# xuefei_zhiye-lab7.net
KiCad netlist of a schematic drawn in EAGLE
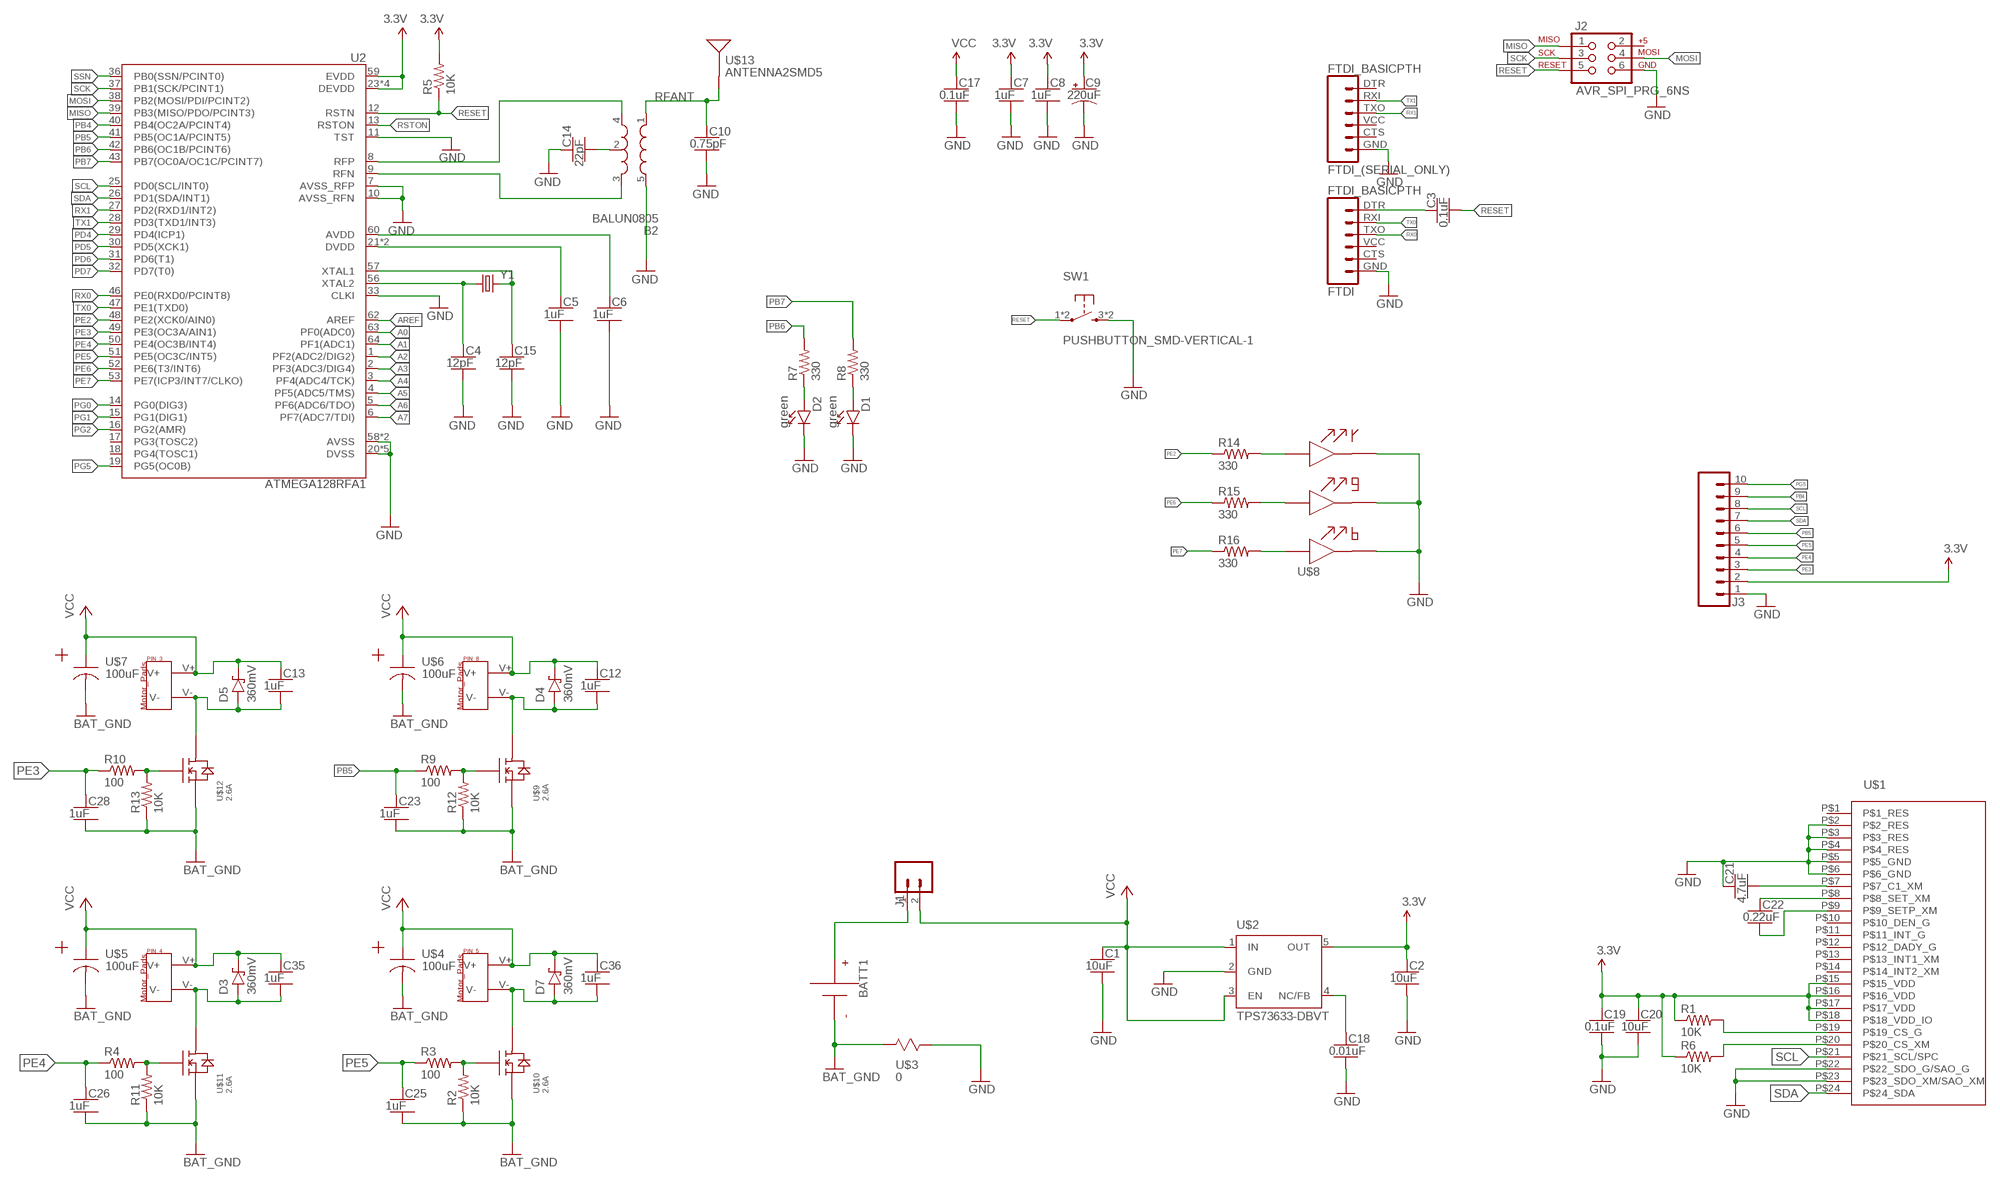
[diagram p0: schematic, sheet 1]

(export (version "E")
  (design (tool "Eeschema 10.0.6"))
  (components
    (comp (ref "B2")
      (value "BALUN0805")
      (footprint "eagle-import:BALUN")
      (fields (field (name "MFR") "Wurth Electronics Inc") (field (name "MPN") "748421245"))
      (libsource (lib "eagle-import") (part "BALUN0805"))
    )
    (comp (ref "BATT1")
      (value "BATTERY-HUBSAN-W/HOLDER")
      (footprint "eagle-import:BATTERY-W_HOLDER-380MAH-HUBSAN")
      (fields
        (field (name "MFR") "HUBSAN")
        (field (name "MPN") "X4-H107C-8-in-1")
        (field (name "CREATOR") "Swanson")
      )
      (libsource (lib "eagle-import") (part "BATTERY-HUBSAN-W/HOLDER"))
    )
    (comp (ref "C1")
      (value "10uF")
      (footprint "eagle-import:CAPC2012X140_HS")
      (fields
        (field (name "MFR") "Murata Electronics North America")
        (field (name "MPN") "GRM21BR61E106KA73L")
      )
      (libsource (lib "eagle-import") (part "CAPACITOR-NP_SMD-2012-0805_CERAMIC-10UF"))
    )
    (comp (ref "C2")
      (value "10uF")
      (footprint "eagle-import:CAPC2012X140_HS")
      (fields
        (field (name "MFR") "Murata Electronics North America")
        (field (name "MPN") "GRM21BR61E106KA73L")
      )
      (libsource (lib "eagle-import") (part "CAPACITOR-NP_SMD-2012-0805_CERAMIC-10UF"))
    )
    (comp (ref "C3")
      (value "0.1uF")
      (footprint "eagle-import:CAPC2012X140_HS")
      (fields
        (field (name "MFR") "Murata Electronics North America")
        (field (name "MPN") "GRM21BR71H104KA01L")
      )
      (libsource (lib "eagle-import") (part "CAPACITOR-NP_SMD-2012-0805_CERAMIC-0.1UF"))
    )
    (comp (ref "C4")
      (value "12pF")
      (footprint "eagle-import:CAPC2012X140_HS")
      (fields
        (field (name "MFR") "Murata Electronics North America")
        (field (name "MPN") "GRM21A5C2E120JW01D")
      )
      (libsource (lib "eagle-import") (part "CAPACITOR-NP_SMD-2012-0805_CERAMIC-12PF"))
    )
    (comp (ref "C5")
      (value "1uF")
      (footprint "eagle-import:CAPC2012X140_HS")
      (fields
        (field (name "MFR") "Murata Electronics North America")
        (field (name "MPN") "GRM21BR71H105KA12L")
      )
      (libsource (lib "eagle-import") (part "CAPACITOR-NP_SMD-2012-0805_CERAMIC-1UF"))
    )
    (comp (ref "C6")
      (value "1uF")
      (footprint "eagle-import:CAPC2012X140_HS")
      (fields
        (field (name "MFR") "Murata Electronics North America")
        (field (name "MPN") "GRM21BR71H105KA12L")
      )
      (libsource (lib "eagle-import") (part "CAPACITOR-NP_SMD-2012-0805_CERAMIC-1UF"))
    )
    (comp (ref "C7")
      (value "1uF")
      (footprint "eagle-import:CAPC2012X140_HS")
      (fields
        (field (name "MFR") "Murata Electronics North America")
        (field (name "MPN") "GRM21BR71H105KA12L")
      )
      (libsource (lib "eagle-import") (part "CAPACITOR-NP_SMD-2012-0805_CERAMIC-1UF"))
    )
    (comp (ref "C8")
      (value "1uF")
      (footprint "eagle-import:CAPC2012X140_HS")
      (fields
        (field (name "MFR") "Murata Electronics North America")
        (field (name "MPN") "GRM21BR71H105KA12L")
      )
      (libsource (lib "eagle-import") (part "CAPACITOR-NP_SMD-2012-0805_CERAMIC-1UF"))
    )
    (comp (ref "C9")
      (value "220uF")
      (footprint "eagle-import:CAPMP7343X310_HS")
      (fields (field (name "MFR") "AVX Corporation") (field (name "MPN") "TAJD227K006RNJ"))
      (libsource (lib "eagle-import") (part "CAPACITOR-POL_SMD-7043-D_TANTALUM-220UF"))
    )
    (comp (ref "C10")
      (value "0.75pF")
      (footprint "eagle-import:CAPC2012X140_HS")
      (fields
        (field (name "MFR") "Murata Electronics North America")
        (field (name "MPN") "GQM2195C2AR75CB01D")
      )
      (libsource (lib "eagle-import") (part "CAPACITOR-NP_SMD-2012-0805_CERAMIC-0.75PF"))
    )
    (comp (ref "C12")
      (value "1uF")
      (footprint "eagle-import:CAPC2012X140_HS")
      (fields
        (field (name "MFR") "Murata Electronics North America")
        (field (name "MPN") "GRM21BR71H105KA12L")
      )
      (libsource (lib "eagle-import") (part "CAPACITOR-NP_SMD-2012-0805_CERAMIC-1UF"))
    )
    (comp (ref "C13")
      (value "1uF")
      (footprint "eagle-import:CAPC2012X140_HS")
      (fields
        (field (name "MFR") "Murata Electronics North America")
        (field (name "MPN") "GRM21BR71H105KA12L")
      )
      (libsource (lib "eagle-import") (part "CAPACITOR-NP_SMD-2012-0805_CERAMIC-1UF"))
    )
    (comp (ref "C14")
      (value "22pF")
      (footprint "eagle-import:CAPC2012X140_HS")
      (fields
        (field (name "MFR") "Murata Electronics North America")
        (field (name "MPN") "GRM21A5C2E220JW01D")
      )
      (libsource (lib "eagle-import") (part "CAPACITOR-NP_SMD-2012-0805_CERAMIC-22PF"))
    )
    (comp (ref "C15")
      (value "12pF")
      (footprint "eagle-import:CAPC2012X140_HS")
      (fields
        (field (name "MFR") "Murata Electronics North America")
        (field (name "MPN") "GRM21A5C2E120JW01D")
      )
      (libsource (lib "eagle-import") (part "CAPACITOR-NP_SMD-2012-0805_CERAMIC-12PF"))
    )
    (comp (ref "C17")
      (value "0.1uF")
      (footprint "eagle-import:CAPC2012X140_HS")
      (fields
        (field (name "MFR") "Murata Electronics North America")
        (field (name "MPN") "GRM21BR71H104KA01L")
      )
      (libsource (lib "eagle-import") (part "CAPACITOR-NP_SMD-2012-0805_CERAMIC-0.1UF"))
    )
    (comp (ref "C18")
      (value "0.01uF")
      (footprint "eagle-import:CAPC2012X140_HS")
      (fields
        (field (name "MFR") "Murata Electronics North America")
        (field (name "MPN") "GRM2195C1H103FA01D")
      )
      (libsource (lib "eagle-import") (part "CAPACITOR-NP_SMD-2012-0805_CERAMIC-0.01UF"))
    )
    (comp (ref "C19")
      (value "0.1uF")
      (footprint "eagle-import:CAPC2012X140_HS")
      (fields
        (field (name "MFR") "Murata Electronics North America")
        (field (name "MPN") "GRM21BR71H104KA01L")
      )
      (libsource (lib "eagle-import") (part "CAPACITOR-NP_SMD-2012-0805_CERAMIC-0.1UF"))
    )
    (comp (ref "C20")
      (value "10uF")
      (footprint "eagle-import:CAPC2012X140_HS")
      (fields
        (field (name "MFR") "Murata Electronics North America")
        (field (name "MPN") "GRM21BR61E106KA73L")
      )
      (libsource (lib "eagle-import") (part "CAPACITOR-NP_SMD-2012-0805_CERAMIC-10UF"))
    )
    (comp (ref "C21")
      (value "4.7uF")
      (footprint "eagle-import:CAPC2012X140_HS")
      (fields
        (field (name "MFR") "Murata Electronics North America")
        (field (name "MPN") "GRM21BR61E475KA12L")
      )
      (libsource (lib "eagle-import") (part "CAPACITOR-NP_SMD-2012-0805_CERAMIC-4.7UF"))
    )
    (comp (ref "C22")
      (value "0.22uF")
      (footprint "eagle-import:CAPC2012X140_HS")
      (fields
        (field (name "MFR") "Murata Electronics North America")
        (field (name "MPN") "GRM21BR71H224KA01L")
      )
      (libsource (lib "eagle-import") (part "CAPACITOR-NP_SMD-2012-0805_CERAMIC-0.22UF"))
    )
    (comp (ref "C23")
      (value "1uF")
      (footprint "eagle-import:CAPC2012X140_HS")
      (fields
        (field (name "MFR") "Murata Electronics North America")
        (field (name "MPN") "GRM21BR71H105KA12L")
      )
      (libsource (lib "eagle-import") (part "CAPACITOR-NP_SMD-2012-0805_CERAMIC-1UF"))
    )
    (comp (ref "C25")
      (value "1uF")
      (footprint "eagle-import:CAPC2012X140_HS")
      (fields
        (field (name "MFR") "Murata Electronics North America")
        (field (name "MPN") "GRM21BR71H105KA12L")
      )
      (libsource (lib "eagle-import") (part "CAPACITOR-NP_SMD-2012-0805_CERAMIC-1UF"))
    )
    (comp (ref "C26")
      (value "1uF")
      (footprint "eagle-import:CAPC2012X140_HS")
      (fields
        (field (name "MFR") "Murata Electronics North America")
        (field (name "MPN") "GRM21BR71H105KA12L")
      )
      (libsource (lib "eagle-import") (part "CAPACITOR-NP_SMD-2012-0805_CERAMIC-1UF"))
    )
    (comp (ref "C28")
      (value "1uF")
      (footprint "eagle-import:CAPC2012X140_HS")
      (fields
        (field (name "MFR") "Murata Electronics North America")
        (field (name "MPN") "GRM21BR71H105KA12L")
      )
      (libsource (lib "eagle-import") (part "CAPACITOR-NP_SMD-2012-0805_CERAMIC-1UF"))
    )
    (comp (ref "C35")
      (value "1uF")
      (footprint "eagle-import:CAPC2012X140_HS")
      (fields
        (field (name "MFR") "Murata Electronics North America")
        (field (name "MPN") "GRM21BR71H105KA12L")
      )
      (libsource (lib "eagle-import") (part "CAPACITOR-NP_SMD-2012-0805_CERAMIC-1UF"))
    )
    (comp (ref "C36")
      (value "1uF")
      (footprint "eagle-import:CAPC2012X140_HS")
      (fields
        (field (name "MFR") "Murata Electronics North America")
        (field (name "MPN") "GRM21BR71H105KA12L")
      )
      (libsource (lib "eagle-import") (part "CAPACITOR-NP_SMD-2012-0805_CERAMIC-1UF"))
    )
    (comp (ref "D1")
      (value "green")
      (footprint "eagle-import:LEDSC125X200X120-2_HS")
      (fields (field (name "MFR") "Lite-On Inc") (field (name "MPN") "LTST-C170GKT"))
      (libsource (lib "eagle-import") (part "DIODE-LED_SMD-2012-0805-GREEN"))
    )
    (comp (ref "D2")
      (value "green")
      (footprint "eagle-import:LEDSC125X200X120-2_HS")
      (fields (field (name "MFR") "Lite-On Inc") (field (name "MPN") "LTST-C170GKT"))
      (libsource (lib "eagle-import") (part "DIODE-LED_SMD-2012-0805-GREEN"))
    )
    (comp (ref "D3")
      (value "360mV")
      (footprint "eagle-import:SOD3716X135_HS")
      (fields
        (field (name "MFR") "Toshiba Semiconductor and Storage")
        (field (name "MPN") "CRS08(TE85L,Q,M)")
      )
      (libsource (lib "eagle-import") (part "DIODE-SCHOTTKY_SMD-SOD123-360MV"))
    )
    (comp (ref "D4")
      (value "360mV")
      (footprint "eagle-import:SOD3716X135_HS")
      (fields
        (field (name "MFR") "Toshiba Semiconductor and Storage")
        (field (name "MPN") "CRS08(TE85L,Q,M)")
      )
      (libsource (lib "eagle-import") (part "DIODE-SCHOTTKY_SMD-SOD123-360MV"))
    )
    (comp (ref "D5")
      (value "360mV")
      (footprint "eagle-import:SOD3716X135_HS")
      (fields
        (field (name "MFR") "Toshiba Semiconductor and Storage")
        (field (name "MPN") "CRS08(TE85L,Q,M)")
      )
      (libsource (lib "eagle-import") (part "DIODE-SCHOTTKY_SMD-SOD123-360MV"))
    )
    (comp (ref "D7")
      (value "360mV")
      (footprint "eagle-import:SOD3716X135_HS")
      (fields
        (field (name "MFR") "Toshiba Semiconductor and Storage")
        (field (name "MPN") "CRS08(TE85L,Q,M)")
      )
      (libsource (lib "eagle-import") (part "DIODE-SCHOTTKY_SMD-SOD123-360MV"))
    )
    (comp (ref "FTDI")
      (value "FTDI_BASICPTH")
      (footprint "eagle-import:FTDI_BASIC")
      (fields (field (name "MFR") "Amphenol FCI") (field (name "MPN") "68016-406HLF"))
      (libsource (lib "eagle-import") (part "FTDI_BASICPTH"))
    )
    (comp (ref "FTDI_(SERIAL_ONLY)")
      (value "FTDI_BASICPTH")
      (footprint "eagle-import:FTDI_BASIC")
      (fields (field (name "MFR") "Amphenol FCI") (field (name "MPN") "68016-406HLF"))
      (libsource (lib "eagle-import") (part "FTDI_BASICPTH"))
    )
    (comp (ref "J1")
      (value "MALE_HEADER_2POS-2X1-0.1IN")
      (footprint "eagle-import:MALE_HEADER_2X1_0.1IN")
      (fields
        (field (name "MFR") "3M")
        (field (name "MPN") "961102-6404-AR")
        (field (name "CREATOR") "SWANSON")
      )
      (libsource (lib "eagle-import") (part "MALE_HEADER_2POS-2X1-0.1IN"))
    )
    (comp (ref "J2")
      (value "AVR_SPI_PRG_6NS")
      (footprint "eagle-import:2X3-NS")
      (fields (field (name "MFR") "Amphenol FCI") (field (name "MPN") "67997-206HLF"))
      (libsource (lib "eagle-import") (part "AVR_SPI_PRG_6NS"))
    )
    (comp (ref "J3")
      (value "SIP-10_TH-254X10-1")
      (footprint "eagle-import:HDRV10W63P254_10X1_2540X254H838_HS")
      (fields (field (name "MFR") "Amphenol FCI") (field (name "MPN") "68000-110HLF"))
      (libsource (lib "eagle-import") (part "SIP-10_TH-254X10-1"))
    )
    (comp (ref "PIN_3")
      (value "MOTOR_PADS")
      (footprint "eagle-import:MOTOR_PADS")
      (fields (field (name "MFR") "NA"))
      (libsource (lib "eagle-import") (part "MOTOR_PADS"))
    )
    (comp (ref "PIN_4")
      (value "MOTOR_PADS")
      (footprint "eagle-import:MOTOR_PADS")
      (fields (field (name "MFR") "NA"))
      (libsource (lib "eagle-import") (part "MOTOR_PADS"))
    )
    (comp (ref "PIN_5")
      (value "MOTOR_PADS")
      (footprint "eagle-import:MOTOR_PADS")
      (fields (field (name "MFR") "NA"))
      (libsource (lib "eagle-import") (part "MOTOR_PADS"))
    )
    (comp (ref "PIN_8")
      (value "MOTOR_PADS")
      (footprint "eagle-import:MOTOR_PADS")
      (fields (field (name "MFR") "NA"))
      (libsource (lib "eagle-import") (part "MOTOR_PADS"))
    )
    (comp (ref "R1")
      (value "10K")
      (footprint "eagle-import:RESC2012X60_HS")
      (fields (field (name "MFR") "Yageo") (field (name "MPN") "RC0805JR-0710KL"))
      (libsource (lib "eagle-import") (part "RESISTOR_SMD-2012-0805-10K"))
    )
    (comp (ref "R2")
      (value "10K")
      (footprint "eagle-import:RESC2012X60_HS")
      (fields (field (name "MFR") "Yageo") (field (name "MPN") "RC0805JR-0710KL"))
      (libsource (lib "eagle-import") (part "RESISTOR_SMD-2012-0805-10K"))
    )
    (comp (ref "R3")
      (value "100")
      (footprint "eagle-import:RESC2012X60_HS")
      (fields (field (name "MFR") "Yageo") (field (name "MPN") "RC0805JR-07100RL"))
      (libsource (lib "eagle-import") (part "RESISTOR_SMD-2012-0805-100"))
    )
    (comp (ref "R4")
      (value "100")
      (footprint "eagle-import:RESC2012X60_HS")
      (fields (field (name "MFR") "Yageo") (field (name "MPN") "RC0805JR-07100RL"))
      (libsource (lib "eagle-import") (part "RESISTOR_SMD-2012-0805-100"))
    )
    (comp (ref "R5")
      (value "10K")
      (footprint "eagle-import:RESC2012X60_HS")
      (fields (field (name "MFR") "Yageo") (field (name "MPN") "RC0805JR-0710KL"))
      (libsource (lib "eagle-import") (part "RESISTOR_SMD-2012-0805-10K"))
    )
    (comp (ref "R6")
      (value "10K")
      (footprint "eagle-import:RESC2012X60_HS")
      (fields (field (name "MFR") "Yageo") (field (name "MPN") "RC0805JR-0710KL"))
      (libsource (lib "eagle-import") (part "RESISTOR_SMD-2012-0805-10K"))
    )
    (comp (ref "R7")
      (value "330")
      (footprint "eagle-import:RESC2012X60_HS")
      (fields (field (name "MFR") "Yageo") (field (name "MPN") "RC0805JR-07330RL"))
      (libsource (lib "eagle-import") (part "RESISTOR_SMD-2012-0805-330"))
    )
    (comp (ref "R8")
      (value "330")
      (footprint "eagle-import:RESC2012X60_HS")
      (fields (field (name "MFR") "Yageo") (field (name "MPN") "RC0805JR-07330RL"))
      (libsource (lib "eagle-import") (part "RESISTOR_SMD-2012-0805-330"))
    )
    (comp (ref "R9")
      (value "100")
      (footprint "eagle-import:RESC2012X60_HS")
      (fields (field (name "MFR") "Yageo") (field (name "MPN") "RC0805JR-07100RL"))
      (libsource (lib "eagle-import") (part "RESISTOR_SMD-2012-0805-100"))
    )
    (comp (ref "R10")
      (value "100")
      (footprint "eagle-import:RESC2012X60_HS")
      (fields (field (name "MFR") "Yageo") (field (name "MPN") "RC0805JR-07100RL"))
      (libsource (lib "eagle-import") (part "RESISTOR_SMD-2012-0805-100"))
    )
    (comp (ref "R11")
      (value "10K")
      (footprint "eagle-import:RESC2012X60_HS")
      (fields (field (name "MFR") "Yageo") (field (name "MPN") "RC0805JR-0710KL"))
      (libsource (lib "eagle-import") (part "RESISTOR_SMD-2012-0805-10K"))
    )
    (comp (ref "R12")
      (value "10K")
      (footprint "eagle-import:RESC2012X60_HS")
      (fields (field (name "MFR") "Yageo") (field (name "MPN") "RC0805JR-0710KL"))
      (libsource (lib "eagle-import") (part "RESISTOR_SMD-2012-0805-10K"))
    )
    (comp (ref "R13")
      (value "10K")
      (footprint "eagle-import:RESC2012X60_HS")
      (fields (field (name "MFR") "Yageo") (field (name "MPN") "RC0805JR-0710KL"))
      (libsource (lib "eagle-import") (part "RESISTOR_SMD-2012-0805-10K"))
    )
    (comp (ref "R14")
      (value "330")
      (footprint "eagle-import:RESC2012X60_HS")
      (fields (field (name "MFR") "Yageo") (field (name "MPN") "RC0805JR-07330RL"))
      (libsource (lib "eagle-import") (part "RESISTOR_SMD-2012-0805-330"))
    )
    (comp (ref "R15")
      (value "330")
      (footprint "eagle-import:RESC2012X60_HS")
      (fields (field (name "MFR") "Yageo") (field (name "MPN") "RC0805JR-07330RL"))
      (libsource (lib "eagle-import") (part "RESISTOR_SMD-2012-0805-330"))
    )
    (comp (ref "R16")
      (value "330")
      (footprint "eagle-import:RESC2012X60_HS")
      (fields (field (name "MFR") "Yageo") (field (name "MPN") "RC0805JR-07330RL"))
      (libsource (lib "eagle-import") (part "RESISTOR_SMD-2012-0805-330"))
    )
    (comp (ref "SW1")
      (value "PUSHBUTTON_SMD-VERTICAL-1")
      (footprint "eagle-import:TE_FSM8JSMA_HS")
      (fields (field (name "MFR") "TE Connectivity Alcoswitch Switches") (field (name "MPN") "FSM4JSMA"))
      (libsource (lib "eagle-import") (part "PUSHBUTTON_SMD-VERTICAL-1"))
    )
    (comp (ref "U$1")
      (value "IMU")
      (footprint "eagle-import:LGA-24_4X4MM")
      (fields
        (field (name "MFR") "STMicroelectronics")
        (field (name "MPN") "LSM9DS0TR")
        (field (name "CREATOR") "Xuefei")
      )
      (libsource (lib "eagle-import") (part "IMU"))
    )
    (comp (ref "U$2")
      (value "TPS73633-DBVT")
      (footprint "eagle-import:SOT23-DBV")
      (fields (field (name "MFR") "Texas Instruments") (field (name "MPN") "LP3985IM5X-3.0/NOPB"))
      (libsource (lib "eagle-import") (part "TPS73633-DBVT"))
    )
    (comp (ref "U$3")
      (value "0")
      (footprint "eagle-import:SMD_RESISTOR")
      (fields
        (field (name "MFR") "Yageo")
        (field (name "MPN") "RC0805JR-070RL")
        (field (name "CREATOR") "Xuefei")
      )
      (libsource (lib "eagle-import") (part "RESISTOR"))
    )
    (comp (ref "U$4")
      (value "100uF")
      (footprint "eagle-import:TAJB_SMB_POLAR_CAP")
      (fields
        (field (name "MFR") "AVX Corporation")
        (field (name "MPN") "TAJB107K006RNJ")
        (field (name "CREATOR") "Xuefei")
      )
      (libsource (lib "eagle-import") (part "POLAR_CAP"))
    )
    (comp (ref "U$5")
      (value "100uF")
      (footprint "eagle-import:TAJB_SMB_POLAR_CAP")
      (fields
        (field (name "MFR") "AVX Corporation")
        (field (name "MPN") "TAJB107K006RNJ")
        (field (name "CREATOR") "Xuefei")
      )
      (libsource (lib "eagle-import") (part "POLAR_CAP"))
    )
    (comp (ref "U$6")
      (value "100uF")
      (footprint "eagle-import:TAJB_SMB_POLAR_CAP")
      (fields
        (field (name "MFR") "AVX Corporation")
        (field (name "MPN") "TAJB107K006RNJ")
        (field (name "CREATOR") "Xuefei")
      )
      (libsource (lib "eagle-import") (part "POLAR_CAP"))
    )
    (comp (ref "U$7")
      (value "100uF")
      (footprint "eagle-import:TAJB_SMB_POLAR_CAP")
      (fields
        (field (name "MFR") "AVX Corporation")
        (field (name "MPN") "TAJB107K006RNJ")
        (field (name "CREATOR") "Xuefei")
      )
      (libsource (lib "eagle-import") (part "POLAR_CAP"))
    )
    (comp (ref "U$8")
      (value "QBLP679E-RGB")
      (footprint "eagle-import:QBLP679E-RGB")
      (fields (field (name "MFR") "QT Brightek (QTB)") (field (name "CREATOR") "Xuefei"))
      (libsource (lib "eagle-import") (part "QBLP679E-RGB"))
    )
    (comp (ref "U$9")
      (value "2.6A")
      (footprint "eagle-import:LITTLE_FOOT_MOSFET_W__HEAT_SPREADER")
      (fields
        (field (name "MFR") "Vishay Siliconix")
        (field (name "MPN") "SI2302CDS-T1-E3")
        (field (name "CREATOR") "Xuefei")
      )
      (libsource (lib "eagle-import") (part "N-CHANNEL_MOSFETW/_HEAT_SINK"))
    )
    (comp (ref "U$10")
      (value "2.6A")
      (footprint "eagle-import:LITTLE_FOOT_MOSFET_W__HEAT_SPREADER")
      (fields
        (field (name "MFR") "Vishay Siliconix")
        (field (name "MPN") "SI2302CDS-T1-E3")
        (field (name "CREATOR") "Xuefei")
      )
      (libsource (lib "eagle-import") (part "N-CHANNEL_MOSFETW/_HEAT_SINK"))
    )
    (comp (ref "U$11")
      (value "2.6A")
      (footprint "eagle-import:LITTLE_FOOT_MOSFET_W__HEAT_SPREADER")
      (fields
        (field (name "MFR") "Vishay Siliconix")
        (field (name "MPN") "SI2302CDS-T1-E3")
        (field (name "CREATOR") "Xuefei")
      )
      (libsource (lib "eagle-import") (part "N-CHANNEL_MOSFETW/_HEAT_SINK"))
    )
    (comp (ref "U$12")
      (value "2.6A")
      (footprint "eagle-import:LITTLE_FOOT_MOSFET_W__HEAT_SPREADER")
      (fields
        (field (name "MFR") "Vishay Siliconix")
        (field (name "MPN") "SI2302CDS-T1-E3")
        (field (name "CREATOR") "Xuefei")
      )
      (libsource (lib "eagle-import") (part "N-CHANNEL_MOSFETW/_HEAT_SINK"))
    )
    (comp (ref "U$13")
      (value "ANTENNA2SMD5")
      (footprint "eagle-import:ANTENNA-CHIP5")
      (fields (field (name "MFR") "Linx Technologies Inc.") (field (name "MPN") "ANT-2.45-CHP-T"))
      (libsource (lib "eagle-import") (part "ANTENNA2SMD5"))
    )
    (comp (ref "U2")
      (value "ATMEGA128RFA1")
      (footprint "eagle-import:QFN-64")
      (fields (field (name "MFR") "Atmel") (field (name "MPN") "ATMEGA128RFA1-ZUR00"))
      (libsource (lib "eagle-import") (part "ATMEGA128RFA1"))
    )
    (comp (ref "Y1")
      (value "CRYSTAL5X3")
      (footprint "eagle-import:CRYSTAL-SMD-5X3")
      (fields (field (name "MFR") "Abracon LLC") (field (name "MPN") "ABM3B-16.000MHZ-B2-T"))
      (libsource (lib "eagle-import") (part "CRYSTAL5X3"))
    )
  )
  (nets
    (net (code "1") (name "/RFANT") (class "Default")
      (node (ref "B2") (pin "1") (pinfunction "IN_1") (pintype "bidirectional"))
      (node (ref "C10") (pin "1") (pinfunction "1_1") (pintype "passive"))
      (node (ref "U$13") (pin "FEED") (pinfunction "SIGNAL_FEED") (pintype "bidirectional"))
    )
    (net (code "2") (name "3.3V") (class "Default")
      (node (ref "C19") (pin "1") (pinfunction "1_1") (pintype "passive"))
      (node (ref "C2") (pin "1") (pinfunction "1_1") (pintype "passive"))
      (node (ref "C20") (pin "1") (pinfunction "1_1") (pintype "passive"))
      (node (ref "C7") (pin "1") (pinfunction "1_1") (pintype "passive"))
      (node (ref "C8") (pin "1") (pinfunction "1_1") (pintype "passive"))
      (node (ref "C9") (pin "1") (pinfunction "+_1") (pintype "passive"))
      (node (ref "J3") (pin "2") (pinfunction "2_2") (pintype "passive"))
      (node (ref "R1") (pin "1") (pinfunction "1_1") (pintype "passive"))
      (node (ref "R5") (pin "2") (pinfunction "2_2") (pintype "passive"))
      (node (ref "R6") (pin "1") (pinfunction "1_1") (pintype "passive"))
      (node (ref "U$1") (pin "P$15") (pinfunction "P$15_VDD_P$15") (pintype "bidirectional"))
      (node (ref "U$1") (pin "P$16") (pinfunction "P$16_VDD_P$16") (pintype "bidirectional"))
      (node (ref "U$1") (pin "P$17") (pinfunction "P$17_VDD_P$17") (pintype "bidirectional"))
      (node (ref "U$1") (pin "P$18") (pinfunction "P$18_VDD_IO_P$18") (pintype "bidirectional"))
      (node (ref "U$2") (pin "5") (pinfunction "OUT_5") (pintype "passive"))
      (node (ref "U2") (pin "23") (pinfunction "DEVDD_23") (pintype "bidirectional"))
      (node (ref "U2") (pin "34") (pinfunction "DEVDD_34") (pintype "bidirectional"))
      (node (ref "U2") (pin "44") (pinfunction "DEVDD_44") (pintype "bidirectional"))
      (node (ref "U2") (pin "54") (pinfunction "DEVDD_54") (pintype "bidirectional"))
      (node (ref "U2") (pin "59") (pinfunction "EVDD_59") (pintype "bidirectional"))
    )
    (net (code "3") (name "A0") (class "Default")
      (node (ref "U2") (pin "63") (pinfunction "PF0(ADC0)_63") (pintype "bidirectional"))
    )
    (net (code "4") (name "A1") (class "Default")
      (node (ref "U2") (pin "64") (pinfunction "PF1(ADC1)_64") (pintype "bidirectional"))
    )
    (net (code "5") (name "A2") (class "Default")
      (node (ref "U2") (pin "1") (pinfunction "PF2(ADC2/DIG2)_1") (pintype "bidirectional"))
    )
    (net (code "6") (name "A3") (class "Default")
      (node (ref "U2") (pin "2") (pinfunction "PF3(ADC3/DIG4)_2") (pintype "bidirectional"))
    )
    (net (code "7") (name "A4") (class "Default")
      (node (ref "U2") (pin "3") (pinfunction "PF4(ADC4/TCK)_3") (pintype "bidirectional"))
    )
    (net (code "8") (name "A5") (class "Default")
      (node (ref "U2") (pin "4") (pinfunction "PF5(ADC5/TMS)_4") (pintype "bidirectional"))
    )
    (net (code "9") (name "A6") (class "Default")
      (node (ref "U2") (pin "5") (pinfunction "PF6(ADC6/TDO)_5") (pintype "bidirectional"))
    )
    (net (code "10") (name "A7") (class "Default")
      (node (ref "U2") (pin "6") (pinfunction "PF7(ADC7/TDI)_6") (pintype "bidirectional"))
    )
    (net (code "11") (name "AREF") (class "Default")
      (node (ref "U2") (pin "62") (pinfunction "AREF_62") (pintype "bidirectional"))
    )
    (net (code "12") (name "BAT_GND") (class "Default")
      (node (ref "BATT1") (pin "-") (pinfunction "N_-") (pintype "bidirectional"))
      (node (ref "C23") (pin "2") (pinfunction "2_2") (pintype "passive"))
      (node (ref "C25") (pin "2") (pinfunction "2_2") (pintype "passive"))
      (node (ref "C26") (pin "2") (pinfunction "2_2") (pintype "passive"))
      (node (ref "C28") (pin "2") (pinfunction "2_2") (pintype "passive"))
      (node (ref "R11") (pin "1") (pinfunction "1_1") (pintype "passive"))
      (node (ref "R12") (pin "1") (pinfunction "1_1") (pintype "passive"))
      (node (ref "R13") (pin "1") (pinfunction "1_1") (pintype "passive"))
      (node (ref "R2") (pin "1") (pinfunction "1_1") (pintype "passive"))
      (node (ref "U$10") (pin "P$2") (pinfunction "P$2_S_P$2") (pintype "bidirectional"))
      (node (ref "U$11") (pin "P$2") (pinfunction "P$2_S_P$2") (pintype "bidirectional"))
      (node (ref "U$12") (pin "P$2") (pinfunction "P$2_S_P$2") (pintype "bidirectional"))
      (node (ref "U$3") (pin "P$1") (pinfunction "P$1_P$1") (pintype "bidirectional"))
      (node (ref "U$4") (pin "P$2") (pinfunction "2_P$2") (pintype "passive"))
      (node (ref "U$5") (pin "P$2") (pinfunction "2_P$2") (pintype "passive"))
      (node (ref "U$6") (pin "P$2") (pinfunction "2_P$2") (pintype "passive"))
      (node (ref "U$7") (pin "P$2") (pinfunction "2_P$2") (pintype "passive"))
      (node (ref "U$9") (pin "P$2") (pinfunction "P$2_S_P$2") (pintype "bidirectional"))
    )
    (net (code "13") (name "GND") (class "Default")
      (node (ref "B2") (pin "5") (pinfunction "GND_5") (pintype "bidirectional"))
      (node (ref "C1") (pin "2") (pinfunction "2_2") (pintype "passive"))
      (node (ref "C10") (pin "2") (pinfunction "2_2") (pintype "passive"))
      (node (ref "C14") (pin "1") (pinfunction "1_1") (pintype "passive"))
      (node (ref "C15") (pin "2") (pinfunction "2_2") (pintype "passive"))
      (node (ref "C17") (pin "2") (pinfunction "2_2") (pintype "passive"))
      (node (ref "C18") (pin "2") (pinfunction "2_2") (pintype "passive"))
      (node (ref "C19") (pin "2") (pinfunction "2_2") (pintype "passive"))
      (node (ref "C2") (pin "2") (pinfunction "2_2") (pintype "passive"))
      (node (ref "C20") (pin "2") (pinfunction "2_2") (pintype "passive"))
      (node (ref "C21") (pin "1") (pinfunction "1_1") (pintype "passive"))
      (node (ref "C4") (pin "2") (pinfunction "2_2") (pintype "passive"))
      (node (ref "C5") (pin "2") (pinfunction "2_2") (pintype "passive"))
      (node (ref "C6") (pin "2") (pinfunction "2_2") (pintype "passive"))
      (node (ref "C7") (pin "2") (pinfunction "2_2") (pintype "passive"))
      (node (ref "C8") (pin "2") (pinfunction "2_2") (pintype "passive"))
      (node (ref "C9") (pin "2") (pinfunction "-_2") (pintype "passive"))
      (node (ref "D1") (pin "C") (pinfunction "C_C") (pintype "passive"))
      (node (ref "D2") (pin "C") (pinfunction "C_C") (pintype "passive"))
      (node (ref "FTDI") (pin "GND") (pinfunction "6_GND") (pintype "passive"))
      (node (ref "FTDI_(SERIAL_ONLY)") (pin "GND") (pinfunction "6_GND") (pintype "passive"))
      (node (ref "J2") (pin "6") (pinfunction "6_6") (pintype "passive"))
      (node (ref "J3") (pin "1") (pinfunction "1_1") (pintype "passive"))
      (node (ref "SW1") (pin "3") (pinfunction "2_3") (pintype "passive"))
      (node (ref "SW1") (pin "4") (pinfunction "2_4") (pintype "passive"))
      (node (ref "U$1") (pin "P$2") (pinfunction "P$2_RES_P$2") (pintype "bidirectional"))
      (node (ref "U$1") (pin "P$22") (pinfunction "P$22_SDO_G/SAO_G_P$22") (pintype "bidirectional"))
      (node (ref "U$1") (pin "P$23") (pinfunction "P$23_SDO_XM/SAO_XM_P$23") (pintype "bidirectional"))
      (node (ref "U$1") (pin "P$3") (pinfunction "P$3_RES_P$3") (pintype "bidirectional"))
      (node (ref "U$1") (pin "P$4") (pinfunction "P$4_RES_P$4") (pintype "bidirectional"))
      (node (ref "U$1") (pin "P$5") (pinfunction "P$5_GND_P$5") (pintype "bidirectional"))
      (node (ref "U$1") (pin "P$6") (pinfunction "P$6_GND_P$6") (pintype "bidirectional"))
      (node (ref "U$2") (pin "2") (pinfunction "GND_2") (pintype "input"))
      (node (ref "U$3") (pin "P$2") (pinfunction "P$2_P$2") (pintype "bidirectional"))
      (node (ref "U$8") (pin "P$1") (pinfunction "P$1_P$1") (pintype "bidirectional"))
      (node (ref "U$8") (pin "P$2") (pinfunction "P$2_P$2") (pintype "bidirectional"))
      (node (ref "U$8") (pin "P$3") (pinfunction "P$3_P$3") (pintype "bidirectional"))
      (node (ref "U2") (pin "10") (pinfunction "AVSS_RFN_10") (pintype "bidirectional"))
      (node (ref "U2") (pin "11") (pinfunction "TST_11") (pintype "bidirectional"))
      (node (ref "U2") (pin "20") (pinfunction "DVSS_20") (pintype "bidirectional"))
      (node (ref "U2") (pin "24") (pinfunction "DVSS_24") (pintype "bidirectional"))
      (node (ref "U2") (pin "33") (pinfunction "CLKI_33") (pintype "bidirectional"))
      (node (ref "U2") (pin "35") (pinfunction "DVSS_35") (pintype "bidirectional"))
      (node (ref "U2") (pin "45") (pinfunction "DVSS_45") (pintype "bidirectional"))
      (node (ref "U2") (pin "55") (pinfunction "DVSS_55") (pintype "bidirectional"))
      (node (ref "U2") (pin "58") (pinfunction "AVSS_58") (pintype "bidirectional"))
      (node (ref "U2") (pin "61") (pinfunction "AVSS_61") (pintype "bidirectional"))
      (node (ref "U2") (pin "7") (pinfunction "AVSS_RFP_7") (pintype "bidirectional"))
    )
    (net (code "14") (name "MISO") (class "Default")
      (node (ref "J2") (pin "1") (pinfunction "1_1") (pintype "passive"))
      (node (ref "U2") (pin "39") (pinfunction "PB3(MISO/PDO/PCINT3)_39") (pintype "bidirectional"))
    )
    (net (code "15") (name "MOSI") (class "Default")
      (node (ref "J2") (pin "4") (pinfunction "4_4") (pintype "passive"))
      (node (ref "U2") (pin "38") (pinfunction "PB2(MOSI/PDI/PCINT2)_38") (pintype "bidirectional"))
    )
    (net (code "16") (name "Net-(B2-GND-Pad2)") (class "Default")
      (node (ref "B2") (pin "2") (pinfunction "GND_2") (pintype "bidirectional"))
      (node (ref "C14") (pin "2") (pinfunction "2_2") (pintype "passive"))
    )
    (net (code "17") (name "Net-(B2-OUT1)") (class "Default")
      (node (ref "B2") (pin "4") (pinfunction "OUT1_4") (pintype "bidirectional"))
      (node (ref "U2") (pin "8") (pinfunction "RFP_8") (pintype "bidirectional"))
    )
    (net (code "18") (name "Net-(B2-OUT2)") (class "Default")
      (node (ref "B2") (pin "3") (pinfunction "OUT2_3") (pintype "bidirectional"))
      (node (ref "U2") (pin "9") (pinfunction "RFN_9") (pintype "bidirectional"))
    )
    (net (code "19") (name "Net-(BATT1-P)") (class "Default")
      (node (ref "BATT1") (pin "+") (pinfunction "P_+") (pintype "bidirectional"))
      (node (ref "J1") (pin "1") (pinfunction "1_1") (pintype "passive"))
    )
    (net (code "20") (name "Net-(C5-Pad1)") (class "Default")
      (node (ref "C5") (pin "1") (pinfunction "1_1") (pintype "passive"))
      (node (ref "U2") (pin "21") (pinfunction "DVDD_21") (pintype "bidirectional"))
      (node (ref "U2") (pin "22") (pinfunction "DVDD_22") (pintype "bidirectional"))
    )
    (net (code "21") (name "Net-(D1-PadA)") (class "Default")
      (node (ref "D1") (pin "A") (pinfunction "A_A") (pintype "passive"))
      (node (ref "R8") (pin "1") (pinfunction "1_1") (pintype "passive"))
    )
    (net (code "22") (name "Net-(D2-PadA)") (class "Default")
      (node (ref "D2") (pin "A") (pinfunction "A_A") (pintype "passive"))
      (node (ref "R7") (pin "1") (pinfunction "1_1") (pintype "passive"))
    )
    (net (code "23") (name "Net-(FTDI-1)") (class "Default")
      (node (ref "C3") (pin "1") (pinfunction "1_1") (pintype "passive"))
      (node (ref "FTDI") (pin "DTR") (pinfunction "1_DTR") (pintype "passive"))
    )
    (net (code "24") (name "Net-(R14-Pad2)") (class "Default")
      (node (ref "R14") (pin "2") (pinfunction "2_2") (pintype "passive"))
      (node (ref "U$8") (pin "P$4") (pinfunction "P$4_P$4") (pintype "bidirectional"))
    )
    (net (code "25") (name "Net-(R15-Pad2)") (class "Default")
      (node (ref "R15") (pin "2") (pinfunction "2_2") (pintype "passive"))
      (node (ref "U$8") (pin "P$5") (pinfunction "P$5_P$5") (pintype "bidirectional"))
    )
    (net (code "26") (name "Net-(R16-Pad2)") (class "Default")
      (node (ref "R16") (pin "2") (pinfunction "2_2") (pintype "passive"))
      (node (ref "U$8") (pin "P$6") (pinfunction "P$6_P$6") (pintype "bidirectional"))
    )
    (net (code "27") (name "Net-(U$1-P$7_C1_XM)") (class "Default")
      (node (ref "C21") (pin "2") (pinfunction "2_2") (pintype "passive"))
      (node (ref "U$1") (pin "P$7") (pinfunction "P$7_C1_XM_P$7") (pintype "bidirectional"))
    )
    (net (code "28") (name "Net-(U$1-P$8_SET_XM)") (class "Default")
      (node (ref "C22") (pin "1") (pinfunction "1_1") (pintype "passive"))
      (node (ref "U$1") (pin "P$8") (pinfunction "P$8_SET_XM_P$8") (pintype "bidirectional"))
    )
    (net (code "29") (name "Net-(U$1-P$9_SETP_XM)") (class "Default")
      (node (ref "C22") (pin "2") (pinfunction "2_2") (pintype "passive"))
      (node (ref "U$1") (pin "P$9") (pinfunction "P$9_SETP_XM_P$9") (pintype "bidirectional"))
    )
    (net (code "30") (name "Net-(U$1-P$19_CS_G)") (class "Default")
      (node (ref "R1") (pin "2") (pinfunction "2_2") (pintype "passive"))
      (node (ref "U$1") (pin "P$19") (pinfunction "P$19_CS_G_P$19") (pintype "bidirectional"))
    )
    (net (code "31") (name "Net-(U$1-P$20_CS_XM)") (class "Default")
      (node (ref "R6") (pin "2") (pinfunction "2_2") (pintype "passive"))
      (node (ref "U$1") (pin "P$20") (pinfunction "P$20_CS_XM_P$20") (pintype "bidirectional"))
    )
    (net (code "32") (name "Net-(U$2-NC{slash}FB)") (class "Default")
      (node (ref "C18") (pin "1") (pinfunction "1_1") (pintype "passive"))
      (node (ref "U$2") (pin "4") (pinfunction "NC/FB_4") (pintype "passive"))
    )
    (net (code "33") (name "Net-(U$9-P$1_G)") (class "Default")
      (node (ref "R12") (pin "2") (pinfunction "2_2") (pintype "passive"))
      (node (ref "R9") (pin "2") (pinfunction "2_2") (pintype "passive"))
      (node (ref "U$9") (pin "P$1") (pinfunction "P$1_G_P$1") (pintype "bidirectional"))
    )
    (net (code "34") (name "Net-(U$9-P$3_D)") (class "Default")
      (node (ref "C12") (pin "2") (pinfunction "2_2") (pintype "passive"))
      (node (ref "D4") (pin "A") (pinfunction "A_A") (pintype "passive"))
      (node (ref "PIN_8") (pin "V-") (pinfunction "V-_V-") (pintype "bidirectional"))
      (node (ref "U$9") (pin "P$3") (pinfunction "P$3_D_P$3") (pintype "bidirectional"))
    )
    (net (code "35") (name "Net-(U$10-P$1_G)") (class "Default")
      (node (ref "R2") (pin "2") (pinfunction "2_2") (pintype "passive"))
      (node (ref "R3") (pin "2") (pinfunction "2_2") (pintype "passive"))
      (node (ref "U$10") (pin "P$1") (pinfunction "P$1_G_P$1") (pintype "bidirectional"))
    )
    (net (code "36") (name "Net-(U$10-P$3_D)") (class "Default")
      (node (ref "C36") (pin "2") (pinfunction "2_2") (pintype "passive"))
      (node (ref "D7") (pin "A") (pinfunction "A_A") (pintype "passive"))
      (node (ref "PIN_5") (pin "V-") (pinfunction "V-_V-") (pintype "bidirectional"))
      (node (ref "U$10") (pin "P$3") (pinfunction "P$3_D_P$3") (pintype "bidirectional"))
    )
    (net (code "37") (name "Net-(U$11-P$1_G)") (class "Default")
      (node (ref "R11") (pin "2") (pinfunction "2_2") (pintype "passive"))
      (node (ref "R4") (pin "2") (pinfunction "2_2") (pintype "passive"))
      (node (ref "U$11") (pin "P$1") (pinfunction "P$1_G_P$1") (pintype "bidirectional"))
    )
    (net (code "38") (name "Net-(U$11-P$3_D)") (class "Default")
      (node (ref "C35") (pin "2") (pinfunction "2_2") (pintype "passive"))
      (node (ref "D3") (pin "A") (pinfunction "A_A") (pintype "passive"))
      (node (ref "PIN_4") (pin "V-") (pinfunction "V-_V-") (pintype "bidirectional"))
      (node (ref "U$11") (pin "P$3") (pinfunction "P$3_D_P$3") (pintype "bidirectional"))
    )
    (net (code "39") (name "Net-(U$12-P$1_G)") (class "Default")
      (node (ref "R10") (pin "2") (pinfunction "2_2") (pintype "passive"))
      (node (ref "R13") (pin "2") (pinfunction "2_2") (pintype "passive"))
      (node (ref "U$12") (pin "P$1") (pinfunction "P$1_G_P$1") (pintype "bidirectional"))
    )
    (net (code "40") (name "Net-(U$12-P$3_D)") (class "Default")
      (node (ref "C13") (pin "2") (pinfunction "2_2") (pintype "passive"))
      (node (ref "D5") (pin "A") (pinfunction "A_A") (pintype "passive"))
      (node (ref "PIN_3") (pin "V-") (pinfunction "V-_V-") (pintype "bidirectional"))
      (node (ref "U$12") (pin "P$3") (pinfunction "P$3_D_P$3") (pintype "bidirectional"))
    )
    (net (code "41") (name "Net-(U2-AVDD)") (class "Default")
      (node (ref "C6") (pin "1") (pinfunction "1_1") (pintype "passive"))
      (node (ref "U2") (pin "60") (pinfunction "AVDD_60") (pintype "bidirectional"))
    )
    (net (code "42") (name "Net-(U2-XTAL1)") (class "Default")
      (node (ref "C15") (pin "1") (pinfunction "1_1") (pintype "passive"))
      (node (ref "U2") (pin "57") (pinfunction "XTAL1_57") (pintype "bidirectional"))
      (node (ref "Y1") (pin "3") (pinfunction "2_3") (pintype "passive"))
    )
    (net (code "43") (name "Net-(U2-XTAL2)") (class "Default")
      (node (ref "C4") (pin "1") (pinfunction "1_1") (pintype "passive"))
      (node (ref "U2") (pin "56") (pinfunction "XTAL2_56") (pintype "bidirectional"))
      (node (ref "Y1") (pin "1") (pinfunction "1_1") (pintype "passive"))
    )
    (net (code "44") (name "PB4") (class "Default")
      (node (ref "J3") (pin "9") (pinfunction "9_9") (pintype "passive"))
      (node (ref "U2") (pin "40") (pinfunction "PB4(OC2A/PCINT4)_40") (pintype "bidirectional"))
    )
    (net (code "45") (name "PB5") (class "Default")
      (node (ref "C23") (pin "1") (pinfunction "1_1") (pintype "passive"))
      (node (ref "J3") (pin "6") (pinfunction "6_6") (pintype "passive"))
      (node (ref "R9") (pin "1") (pinfunction "1_1") (pintype "passive"))
      (node (ref "U2") (pin "41") (pinfunction "PB5(OC1A/PCINT5)_41") (pintype "bidirectional"))
    )
    (net (code "46") (name "PB6") (class "Default")
      (node (ref "R7") (pin "2") (pinfunction "2_2") (pintype "passive"))
      (node (ref "U2") (pin "42") (pinfunction "PB6(OC1B/PCINT6)_42") (pintype "bidirectional"))
    )
    (net (code "47") (name "PB7") (class "Default")
      (node (ref "R8") (pin "2") (pinfunction "2_2") (pintype "passive"))
      (node (ref "U2") (pin "43") (pinfunction "PB7(OC0A/OC1C/PCINT7)_43") (pintype "bidirectional"))
    )
    (net (code "48") (name "PD4") (class "Default")
      (node (ref "U2") (pin "29") (pinfunction "PD4(ICP1)_29") (pintype "bidirectional"))
    )
    (net (code "49") (name "PD5") (class "Default")
      (node (ref "U2") (pin "30") (pinfunction "PD5(XCK1)_30") (pintype "bidirectional"))
    )
    (net (code "50") (name "PD6") (class "Default")
      (node (ref "U2") (pin "31") (pinfunction "PD6(T1)_31") (pintype "bidirectional"))
    )
    (net (code "51") (name "PD7") (class "Default")
      (node (ref "U2") (pin "32") (pinfunction "PD7(T0)_32") (pintype "bidirectional"))
    )
    (net (code "52") (name "PE2") (class "Default")
      (node (ref "R14") (pin "1") (pinfunction "1_1") (pintype "passive"))
      (node (ref "U2") (pin "48") (pinfunction "PE2(XCK0/AIN0)_48") (pintype "bidirectional"))
    )
    (net (code "53") (name "PE3") (class "Default")
      (node (ref "C28") (pin "1") (pinfunction "1_1") (pintype "passive"))
      (node (ref "J3") (pin "3") (pinfunction "3_3") (pintype "passive"))
      (node (ref "R10") (pin "1") (pinfunction "1_1") (pintype "passive"))
      (node (ref "U2") (pin "49") (pinfunction "PE3(OC3A/AIN1)_49") (pintype "bidirectional"))
    )
    (net (code "54") (name "PE4") (class "Default")
      (node (ref "C26") (pin "1") (pinfunction "1_1") (pintype "passive"))
      (node (ref "J3") (pin "4") (pinfunction "4_4") (pintype "passive"))
      (node (ref "R4") (pin "1") (pinfunction "1_1") (pintype "passive"))
      (node (ref "U2") (pin "50") (pinfunction "PE4(OC3B/INT4)_50") (pintype "bidirectional"))
    )
    (net (code "55") (name "PE5") (class "Default")
      (node (ref "C25") (pin "1") (pinfunction "1_1") (pintype "passive"))
      (node (ref "J3") (pin "5") (pinfunction "5_5") (pintype "passive"))
      (node (ref "R3") (pin "1") (pinfunction "1_1") (pintype "passive"))
      (node (ref "U2") (pin "51") (pinfunction "PE5(OC3C/INT5)_51") (pintype "bidirectional"))
    )
    (net (code "56") (name "PE6") (class "Default")
      (node (ref "R15") (pin "1") (pinfunction "1_1") (pintype "passive"))
      (node (ref "U2") (pin "52") (pinfunction "PE6(T3/INT6)_52") (pintype "bidirectional"))
    )
    (net (code "57") (name "PE7") (class "Default")
      (node (ref "R16") (pin "1") (pinfunction "1_1") (pintype "passive"))
      (node (ref "U2") (pin "53") (pinfunction "PE7(ICP3/INT7/CLKO)_53") (pintype "bidirectional"))
    )
    (net (code "58") (name "PG0") (class "Default")
      (node (ref "U2") (pin "14") (pinfunction "PG0(DIG3)_14") (pintype "bidirectional"))
    )
    (net (code "59") (name "PG1") (class "Default")
      (node (ref "U2") (pin "15") (pinfunction "PG1(DIG1)_15") (pintype "bidirectional"))
    )
    (net (code "60") (name "PG2") (class "Default")
      (node (ref "U2") (pin "16") (pinfunction "PG2(AMR)_16") (pintype "bidirectional"))
    )
    (net (code "61") (name "PG5") (class "Default")
      (node (ref "J3") (pin "10") (pinfunction "10_10") (pintype "passive"))
      (node (ref "U2") (pin "19") (pinfunction "PG5(OC0B)_19") (pintype "bidirectional"))
    )
    (net (code "62") (name "RESET") (class "Default")
      (node (ref "C3") (pin "2") (pinfunction "2_2") (pintype "passive"))
      (node (ref "J2") (pin "5") (pinfunction "5_5") (pintype "passive"))
      (node (ref "R5") (pin "1") (pinfunction "1_1") (pintype "passive"))
      (node (ref "SW1") (pin "1") (pinfunction "1_1") (pintype "passive"))
      (node (ref "SW1") (pin "2") (pinfunction "1_2") (pintype "passive"))
      (node (ref "U2") (pin "12") (pinfunction "RSTN_12") (pintype "bidirectional"))
    )
    (net (code "63") (name "RSTON") (class "Default")
      (node (ref "U2") (pin "13") (pinfunction "RSTON_13") (pintype "bidirectional"))
    )
    (net (code "64") (name "RX0") (class "Default")
      (node (ref "FTDI") (pin "TXO") (pinfunction "3_TXO") (pintype "passive"))
      (node (ref "U2") (pin "46") (pinfunction "PE0(RXD0/PCINT8)_46") (pintype "bidirectional"))
    )
    (net (code "65") (name "RX1") (class "Default")
      (node (ref "FTDI_(SERIAL_ONLY)") (pin "TXO") (pinfunction "3_TXO") (pintype "passive"))
      (node (ref "U2") (pin "27") (pinfunction "PD2(RXD1/INT2)_27") (pintype "bidirectional"))
    )
    (net (code "66") (name "SCK") (class "Default")
      (node (ref "J2") (pin "3") (pinfunction "3_3") (pintype "passive"))
      (node (ref "U2") (pin "37") (pinfunction "PB1(SCK/PCINT1)_37") (pintype "bidirectional"))
    )
    (net (code "67") (name "SCL") (class "Default")
      (node (ref "J3") (pin "8") (pinfunction "8_8") (pintype "passive"))
      (node (ref "U$1") (pin "P$21") (pinfunction "P$21_SCL/SPC_P$21") (pintype "bidirectional"))
      (node (ref "U2") (pin "25") (pinfunction "PD0(SCL/INT0)_25") (pintype "bidirectional"))
    )
    (net (code "68") (name "SDA") (class "Default")
      (node (ref "J3") (pin "7") (pinfunction "7_7") (pintype "passive"))
      (node (ref "U$1") (pin "P$24") (pinfunction "P$24_SDA_P$24") (pintype "bidirectional"))
      (node (ref "U2") (pin "26") (pinfunction "PD1(SDA/INT1)_26") (pintype "bidirectional"))
    )
    (net (code "69") (name "SSN") (class "Default")
      (node (ref "U2") (pin "36") (pinfunction "PB0(SSN/PCINT0)_36") (pintype "bidirectional"))
    )
    (net (code "70") (name "TX0") (class "Default")
      (node (ref "FTDI") (pin "RXI") (pinfunction "2_RXI") (pintype "passive"))
      (node (ref "U2") (pin "47") (pinfunction "PE1(TXD0)_47") (pintype "bidirectional"))
    )
    (net (code "71") (name "TX1") (class "Default")
      (node (ref "FTDI_(SERIAL_ONLY)") (pin "RXI") (pinfunction "2_RXI") (pintype "passive"))
      (node (ref "U2") (pin "28") (pinfunction "PD3(TXD1/INT3)_28") (pintype "bidirectional"))
    )
    (net (code "72") (name "VCC") (class "Default")
      (node (ref "C1") (pin "1") (pinfunction "1_1") (pintype "passive"))
      (node (ref "C12") (pin "1") (pinfunction "1_1") (pintype "passive"))
      (node (ref "C13") (pin "1") (pinfunction "1_1") (pintype "passive"))
      (node (ref "C17") (pin "1") (pinfunction "1_1") (pintype "passive"))
      (node (ref "C35") (pin "1") (pinfunction "1_1") (pintype "passive"))
      (node (ref "C36") (pin "1") (pinfunction "1_1") (pintype "passive"))
      (node (ref "D3") (pin "C") (pinfunction "C_C") (pintype "passive"))
      (node (ref "D4") (pin "C") (pinfunction "C_C") (pintype "passive"))
      (node (ref "D5") (pin "C") (pinfunction "C_C") (pintype "passive"))
      (node (ref "D7") (pin "C") (pinfunction "C_C") (pintype "passive"))
      (node (ref "J1") (pin "2") (pinfunction "2_2") (pintype "passive"))
      (node (ref "PIN_3") (pin "V+") (pinfunction "V+_V+") (pintype "bidirectional"))
      (node (ref "PIN_4") (pin "V+") (pinfunction "V+_V+") (pintype "bidirectional"))
      (node (ref "PIN_5") (pin "V+") (pinfunction "V+_V+") (pintype "bidirectional"))
      (node (ref "PIN_8") (pin "V+") (pinfunction "V+_V+") (pintype "bidirectional"))
      (node (ref "U$2") (pin "1") (pinfunction "IN_1") (pintype "input"))
      (node (ref "U$2") (pin "3") (pinfunction "EN_3") (pintype "input"))
      (node (ref "U$4") (pin "P$1") (pinfunction "1_P$1") (pintype "passive"))
      (node (ref "U$5") (pin "P$1") (pinfunction "1_P$1") (pintype "passive"))
      (node (ref "U$6") (pin "P$1") (pinfunction "1_P$1") (pintype "passive"))
      (node (ref "U$7") (pin "P$1") (pinfunction "1_P$1") (pintype "passive"))
    )
    (net (code "73") (name "unconnected-(FTDI-4-PadVCC)") (class "Default")
      (node (ref "FTDI") (pin "VCC") (pinfunction "4_VCC") (pintype "passive"))
    )
    (net (code "74") (name "unconnected-(FTDI-5-PadCTS)") (class "Default")
      (node (ref "FTDI") (pin "CTS") (pinfunction "5_CTS") (pintype "passive"))
    )
    (net (code "75") (name "unconnected-(FTDI_(SERIAL_ONLY)-1-PadDTR)") (class "Default")
      (node (ref "FTDI_(SERIAL_ONLY)") (pin "DTR") (pinfunction "1_DTR") (pintype "passive"))
    )
    (net (code "76") (name "unconnected-(FTDI_(SERIAL_ONLY)-4-PadVCC)") (class "Default")
      (node (ref "FTDI_(SERIAL_ONLY)") (pin "VCC") (pinfunction "4_VCC") (pintype "passive"))
    )
    (net (code "77") (name "unconnected-(FTDI_(SERIAL_ONLY)-5-PadCTS)") (class "Default")
      (node (ref "FTDI_(SERIAL_ONLY)") (pin "CTS") (pinfunction "5_CTS") (pintype "passive"))
    )
    (net (code "78") (name "unconnected-(J2-Pad2)") (class "Default")
      (node (ref "J2") (pin "2") (pinfunction "2_2") (pintype "passive"))
    )
    (net (code "79") (name "unconnected-(U$1-P$1_RES-PadP$1)") (class "Default")
      (node (ref "U$1") (pin "P$1") (pinfunction "P$1_RES_P$1") (pintype "bidirectional"))
    )
    (net (code "80") (name "unconnected-(U$1-P$10_DEN_G-PadP$10)") (class "Default")
      (node (ref "U$1") (pin "P$10") (pinfunction "P$10_DEN_G_P$10") (pintype "bidirectional"))
    )
    (net (code "81") (name "unconnected-(U$1-P$11_INT_G-PadP$11)") (class "Default")
      (node (ref "U$1") (pin "P$11") (pinfunction "P$11_INT_G_P$11") (pintype "bidirectional"))
    )
    (net (code "82") (name "unconnected-(U$1-P$12_DADY_G-PadP$12)") (class "Default")
      (node (ref "U$1") (pin "P$12") (pinfunction "P$12_DADY_G_P$12") (pintype "bidirectional"))
    )
    (net (code "83") (name "unconnected-(U$1-P$13_INT1_XM-PadP$13)") (class "Default")
      (node (ref "U$1") (pin "P$13") (pinfunction "P$13_INT1_XM_P$13") (pintype "bidirectional"))
    )
    (net (code "84") (name "unconnected-(U$1-P$14_INT2_XM-PadP$14)") (class "Default")
      (node (ref "U$1") (pin "P$14") (pinfunction "P$14_INT2_XM_P$14") (pintype "bidirectional"))
    )
    (net (code "85") (name "unconnected-(U2-PG3(TOSC2)-Pad17)") (class "Default")
      (node (ref "U2") (pin "17") (pinfunction "PG3(TOSC2)_17") (pintype "bidirectional"))
    )
    (net (code "86") (name "unconnected-(U2-PG4(TOSC1)-Pad18)") (class "Default")
      (node (ref "U2") (pin "18") (pinfunction "PG4(TOSC1)_18") (pintype "bidirectional"))
    )
  )
)
